# untitled.net
KiCad netlist of a schematic drawn in EAGLE
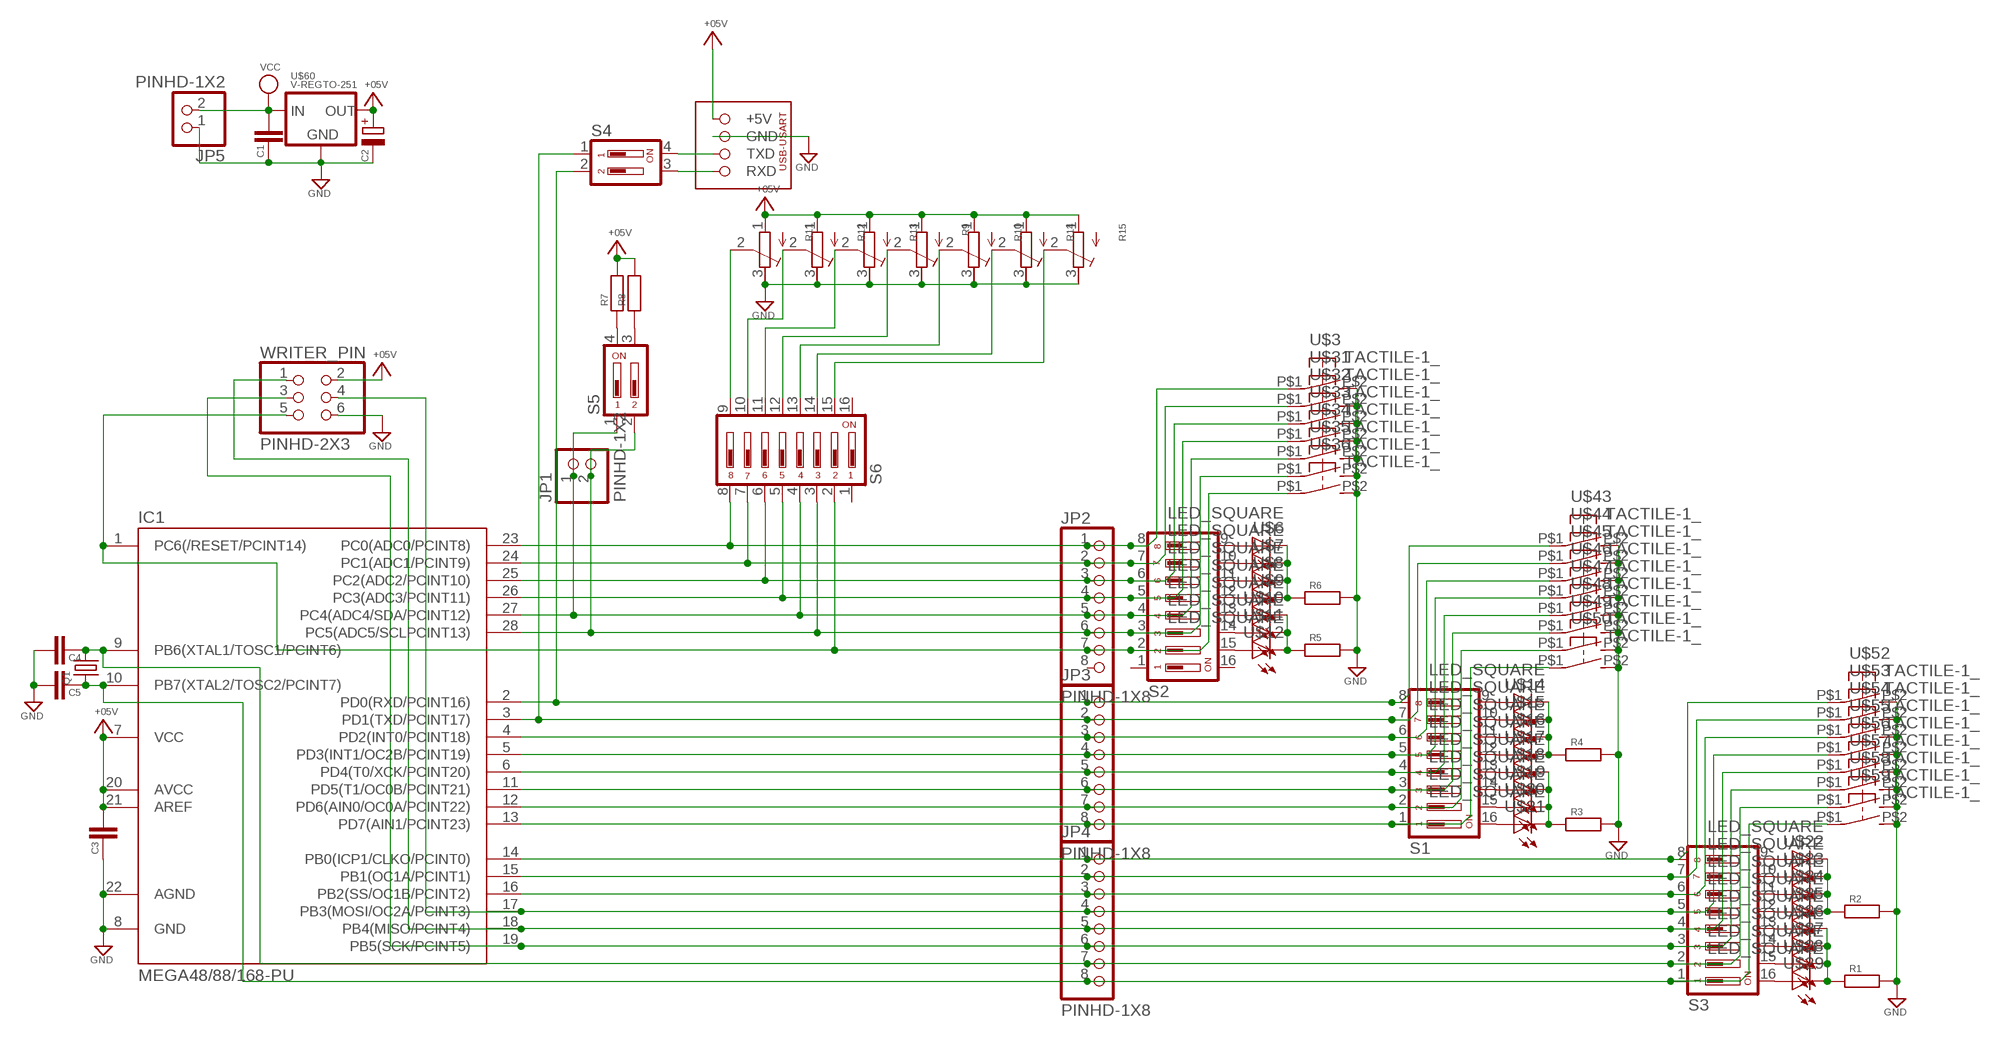
[diagram p0: schematic, sheet 1]

(export (version "E")
  (design (tool "Eeschema 10.0.6"))
  (components
    (comp (ref "C1")
      (value "C-025-025X050")
      (footprint "eagle-import:C025-025X050")
      (libsource (lib "eagle-import") (part "C-025-025X050"))
    )
    (comp (ref "C2")
      (value "CPOL-E2.5-6")
      (footprint "eagle-import:E2,5-6")
      (libsource (lib "eagle-import") (part "CPOL-E2.5-6"))
    )
    (comp (ref "C3")
      (value "C-025-025X050")
      (footprint "eagle-import:C025-025X050")
      (libsource (lib "eagle-import") (part "C-025-025X050"))
    )
    (comp (ref "C4")
      (value "C-025-025X050")
      (footprint "eagle-import:C025-025X050")
      (libsource (lib "eagle-import") (part "C-025-025X050"))
    )
    (comp (ref "C5")
      (value "C-025-025X050")
      (footprint "eagle-import:C025-025X050")
      (libsource (lib "eagle-import") (part "C-025-025X050"))
    )
    (comp (ref "IC1")
      (value "MEGA48/88/168-PU")
      (footprint "eagle-import:DIL28-3")
      (libsource (lib "eagle-import") (part "MEGA48/88/168-PU"))
    )
    (comp (ref "JP1")
      (value "PINHD-1X2")
      (footprint "eagle-import:1X02")
      (libsource (lib "eagle-import") (part "PINHD-1X2"))
    )
    (comp (ref "JP2")
      (value "PINHD-1X8")
      (footprint "eagle-import:1X08")
      (libsource (lib "eagle-import") (part "PINHD-1X8"))
    )
    (comp (ref "JP3")
      (value "PINHD-1X8")
      (footprint "eagle-import:1X08")
      (libsource (lib "eagle-import") (part "PINHD-1X8"))
    )
    (comp (ref "JP4")
      (value "PINHD-1X8")
      (footprint "eagle-import:1X08")
      (libsource (lib "eagle-import") (part "PINHD-1X8"))
    )
    (comp (ref "JP5")
      (value "PINHD-1X2")
      (footprint "eagle-import:1X02")
      (libsource (lib "eagle-import") (part "PINHD-1X2"))
    )
    (comp (ref "Q1")
      (value "CRYSTALHC49S")
      (footprint "eagle-import:HC49_S")
      (libsource (lib "eagle-import") (part "CRYSTALHC49S"))
    )
    (comp (ref "R1")
      (value "R-EU_1/4W(8MM)")
      (footprint "eagle-import:1_4W(8MM)")
      (libsource (lib "eagle-import") (part "R-EU_1/4W(8MM)"))
    )
    (comp (ref "R2")
      (value "R-EU_1/4W(8MM)")
      (footprint "eagle-import:1_4W(8MM)")
      (libsource (lib "eagle-import") (part "R-EU_1/4W(8MM)"))
    )
    (comp (ref "R3")
      (value "R-EU_1/4W(8MM)")
      (footprint "eagle-import:1_4W(8MM)")
      (libsource (lib "eagle-import") (part "R-EU_1/4W(8MM)"))
    )
    (comp (ref "R4")
      (value "R-EU_1/4W(8MM)")
      (footprint "eagle-import:1_4W(8MM)")
      (libsource (lib "eagle-import") (part "R-EU_1/4W(8MM)"))
    )
    (comp (ref "R5")
      (value "R-EU_1/4W(8MM)")
      (footprint "eagle-import:1_4W(8MM)")
      (libsource (lib "eagle-import") (part "R-EU_1/4W(8MM)"))
    )
    (comp (ref "R6")
      (value "R-EU_1/4W(8MM)")
      (footprint "eagle-import:1_4W(8MM)")
      (libsource (lib "eagle-import") (part "R-EU_1/4W(8MM)"))
    )
    (comp (ref "R7")
      (value "R-EU_1/4W(8MM)")
      (footprint "eagle-import:1_4W(8MM)")
      (libsource (lib "eagle-import") (part "R-EU_1/4W(8MM)"))
    )
    (comp (ref "R8")
      (value "R-EU_1/4W(8MM)")
      (footprint "eagle-import:1_4W(8MM)")
      (libsource (lib "eagle-import") (part "R-EU_1/4W(8MM)"))
    )
    (comp (ref "R9")
      (value "R-TRIMM_3339P")
      (footprint "eagle-import:3339P")
      (libsource (lib "eagle-import") (part "R-TRIMM_3339P"))
    )
    (comp (ref "R10")
      (value "R-TRIMM_3339P")
      (footprint "eagle-import:3339P")
      (libsource (lib "eagle-import") (part "R-TRIMM_3339P"))
    )
    (comp (ref "R11")
      (value "R-TRIMM_3339P")
      (footprint "eagle-import:3339P")
      (libsource (lib "eagle-import") (part "R-TRIMM_3339P"))
    )
    (comp (ref "R12")
      (value "R-TRIMM_3339P")
      (footprint "eagle-import:3339P")
      (libsource (lib "eagle-import") (part "R-TRIMM_3339P"))
    )
    (comp (ref "R13")
      (value "R-TRIMM_3339P")
      (footprint "eagle-import:3339P")
      (libsource (lib "eagle-import") (part "R-TRIMM_3339P"))
    )
    (comp (ref "R14")
      (value "R-TRIMM_3339P")
      (footprint "eagle-import:3339P")
      (libsource (lib "eagle-import") (part "R-TRIMM_3339P"))
    )
    (comp (ref "R15")
      (value "R-TRIMM_3339P")
      (footprint "eagle-import:3339P")
      (libsource (lib "eagle-import") (part "R-TRIMM_3339P"))
    )
    (comp (ref "S1")
      (value "DIP08YL")
      (footprint "eagle-import:DIP08YL")
      (libsource (lib "eagle-import") (part "DIP08YL"))
    )
    (comp (ref "S2")
      (value "DIP08YL")
      (footprint "eagle-import:DIP08YL")
      (libsource (lib "eagle-import") (part "DIP08YL"))
    )
    (comp (ref "S3")
      (value "DIP08YL")
      (footprint "eagle-import:DIP08YL")
      (libsource (lib "eagle-import") (part "DIP08YL"))
    )
    (comp (ref "S4")
      (value "DIP02YL")
      (footprint "eagle-import:DIP02YL")
      (libsource (lib "eagle-import") (part "DIP02YL"))
    )
    (comp (ref "S5")
      (value "DIP02YL")
      (footprint "eagle-import:DIP02YL")
      (libsource (lib "eagle-import") (part "DIP02YL"))
    )
    (comp (ref "S6")
      (value "DIP08YL")
      (footprint "eagle-import:DIP08YL")
      (libsource (lib "eagle-import") (part "DIP08YL"))
    )
    (comp (ref "U$3")
      (value "TACTILE-1_")
      (footprint "eagle-import:TACTILE_")
      (libsource (lib "eagle-import") (part "TACTILE-1_"))
    )
    (comp (ref "U$6")
      (value "LED_SQUARE")
      (footprint "eagle-import:5020")
      (libsource (lib "eagle-import") (part "LED_SQUARE"))
    )
    (comp (ref "U$7")
      (value "LED_SQUARE")
      (footprint "eagle-import:5020")
      (libsource (lib "eagle-import") (part "LED_SQUARE"))
    )
    (comp (ref "U$8")
      (value "LED_SQUARE")
      (footprint "eagle-import:5020")
      (libsource (lib "eagle-import") (part "LED_SQUARE"))
    )
    (comp (ref "U$9")
      (value "LED_SQUARE")
      (footprint "eagle-import:5020")
      (libsource (lib "eagle-import") (part "LED_SQUARE"))
    )
    (comp (ref "U$10")
      (value "LED_SQUARE")
      (footprint "eagle-import:5020")
      (libsource (lib "eagle-import") (part "LED_SQUARE"))
    )
    (comp (ref "U$11")
      (value "LED_SQUARE")
      (footprint "eagle-import:5020")
      (libsource (lib "eagle-import") (part "LED_SQUARE"))
    )
    (comp (ref "U$12")
      (value "LED_SQUARE")
      (footprint "eagle-import:5020")
      (libsource (lib "eagle-import") (part "LED_SQUARE"))
    )
    (comp (ref "U$14")
      (value "LED_SQUARE")
      (footprint "eagle-import:5020")
      (libsource (lib "eagle-import") (part "LED_SQUARE"))
    )
    (comp (ref "U$15")
      (value "LED_SQUARE")
      (footprint "eagle-import:5020")
      (libsource (lib "eagle-import") (part "LED_SQUARE"))
    )
    (comp (ref "U$16")
      (value "LED_SQUARE")
      (footprint "eagle-import:5020")
      (libsource (lib "eagle-import") (part "LED_SQUARE"))
    )
    (comp (ref "U$17")
      (value "LED_SQUARE")
      (footprint "eagle-import:5020")
      (libsource (lib "eagle-import") (part "LED_SQUARE"))
    )
    (comp (ref "U$18")
      (value "LED_SQUARE")
      (footprint "eagle-import:5020")
      (libsource (lib "eagle-import") (part "LED_SQUARE"))
    )
    (comp (ref "U$19")
      (value "LED_SQUARE")
      (footprint "eagle-import:5020")
      (libsource (lib "eagle-import") (part "LED_SQUARE"))
    )
    (comp (ref "U$20")
      (value "LED_SQUARE")
      (footprint "eagle-import:5020")
      (libsource (lib "eagle-import") (part "LED_SQUARE"))
    )
    (comp (ref "U$21")
      (value "LED_SQUARE")
      (footprint "eagle-import:5020")
      (libsource (lib "eagle-import") (part "LED_SQUARE"))
    )
    (comp (ref "U$22")
      (value "LED_SQUARE")
      (footprint "eagle-import:5020")
      (libsource (lib "eagle-import") (part "LED_SQUARE"))
    )
    (comp (ref "U$23")
      (value "LED_SQUARE")
      (footprint "eagle-import:5020")
      (libsource (lib "eagle-import") (part "LED_SQUARE"))
    )
    (comp (ref "U$24")
      (value "LED_SQUARE")
      (footprint "eagle-import:5020")
      (libsource (lib "eagle-import") (part "LED_SQUARE"))
    )
    (comp (ref "U$25")
      (value "LED_SQUARE")
      (footprint "eagle-import:5020")
      (libsource (lib "eagle-import") (part "LED_SQUARE"))
    )
    (comp (ref "U$26")
      (value "LED_SQUARE")
      (footprint "eagle-import:5020")
      (libsource (lib "eagle-import") (part "LED_SQUARE"))
    )
    (comp (ref "U$27")
      (value "LED_SQUARE")
      (footprint "eagle-import:5020")
      (libsource (lib "eagle-import") (part "LED_SQUARE"))
    )
    (comp (ref "U$28")
      (value "LED_SQUARE")
      (footprint "eagle-import:5020")
      (libsource (lib "eagle-import") (part "LED_SQUARE"))
    )
    (comp (ref "U$29")
      (value "LED_SQUARE")
      (footprint "eagle-import:5020")
      (libsource (lib "eagle-import") (part "LED_SQUARE"))
    )
    (comp (ref "U$31")
      (value "TACTILE-1_")
      (footprint "eagle-import:TACTILE_")
      (libsource (lib "eagle-import") (part "TACTILE-1_"))
    )
    (comp (ref "U$32")
      (value "TACTILE-1_")
      (footprint "eagle-import:TACTILE_")
      (libsource (lib "eagle-import") (part "TACTILE-1_"))
    )
    (comp (ref "U$33")
      (value "TACTILE-1_")
      (footprint "eagle-import:TACTILE_")
      (libsource (lib "eagle-import") (part "TACTILE-1_"))
    )
    (comp (ref "U$34")
      (value "TACTILE-1_")
      (footprint "eagle-import:TACTILE_")
      (libsource (lib "eagle-import") (part "TACTILE-1_"))
    )
    (comp (ref "U$35")
      (value "TACTILE-1_")
      (footprint "eagle-import:TACTILE_")
      (libsource (lib "eagle-import") (part "TACTILE-1_"))
    )
    (comp (ref "U$36")
      (value "TACTILE-1_")
      (footprint "eagle-import:TACTILE_")
      (libsource (lib "eagle-import") (part "TACTILE-1_"))
    )
    (comp (ref "U$43")
      (value "TACTILE-1_")
      (footprint "eagle-import:TACTILE_")
      (libsource (lib "eagle-import") (part "TACTILE-1_"))
    )
    (comp (ref "U$44")
      (value "TACTILE-1_")
      (footprint "eagle-import:TACTILE_")
      (libsource (lib "eagle-import") (part "TACTILE-1_"))
    )
    (comp (ref "U$45")
      (value "TACTILE-1_")
      (footprint "eagle-import:TACTILE_")
      (libsource (lib "eagle-import") (part "TACTILE-1_"))
    )
    (comp (ref "U$46")
      (value "TACTILE-1_")
      (footprint "eagle-import:TACTILE_")
      (libsource (lib "eagle-import") (part "TACTILE-1_"))
    )
    (comp (ref "U$47")
      (value "TACTILE-1_")
      (footprint "eagle-import:TACTILE_")
      (libsource (lib "eagle-import") (part "TACTILE-1_"))
    )
    (comp (ref "U$48")
      (value "TACTILE-1_")
      (footprint "eagle-import:TACTILE_")
      (libsource (lib "eagle-import") (part "TACTILE-1_"))
    )
    (comp (ref "U$49")
      (value "TACTILE-1_")
      (footprint "eagle-import:TACTILE_")
      (libsource (lib "eagle-import") (part "TACTILE-1_"))
    )
    (comp (ref "U$50")
      (value "TACTILE-1_")
      (footprint "eagle-import:TACTILE_")
      (libsource (lib "eagle-import") (part "TACTILE-1_"))
    )
    (comp (ref "U$52")
      (value "TACTILE-1_")
      (footprint "eagle-import:TACTILE_")
      (libsource (lib "eagle-import") (part "TACTILE-1_"))
    )
    (comp (ref "U$53")
      (value "TACTILE-1_")
      (footprint "eagle-import:TACTILE_")
      (libsource (lib "eagle-import") (part "TACTILE-1_"))
    )
    (comp (ref "U$54")
      (value "TACTILE-1_")
      (footprint "eagle-import:TACTILE_")
      (libsource (lib "eagle-import") (part "TACTILE-1_"))
    )
    (comp (ref "U$55")
      (value "TACTILE-1_")
      (footprint "eagle-import:TACTILE_")
      (libsource (lib "eagle-import") (part "TACTILE-1_"))
    )
    (comp (ref "U$56")
      (value "TACTILE-1_")
      (footprint "eagle-import:TACTILE_")
      (libsource (lib "eagle-import") (part "TACTILE-1_"))
    )
    (comp (ref "U$57")
      (value "TACTILE-1_")
      (footprint "eagle-import:TACTILE_")
      (libsource (lib "eagle-import") (part "TACTILE-1_"))
    )
    (comp (ref "U$58")
      (value "TACTILE-1_")
      (footprint "eagle-import:TACTILE_")
      (libsource (lib "eagle-import") (part "TACTILE-1_"))
    )
    (comp (ref "U$59")
      (value "TACTILE-1_")
      (footprint "eagle-import:TACTILE_")
      (libsource (lib "eagle-import") (part "TACTILE-1_"))
    )
    (comp (ref "U$60")
      (value "V-REGTO-251")
      (footprint "eagle-import:TO-251")
      (libsource (lib "eagle-import") (part "V-REGTO-251"))
    )
    (comp (ref "U$64")
      (value "AE-FT234X")
      (footprint "eagle-import:AE-FT234X")
      (libsource (lib "eagle-import") (part "AE-FT234X"))
    )
    (comp (ref "WRITER_PIN")
      (value "PINHD-2X3")
      (footprint "eagle-import:2X03")
      (libsource (lib "eagle-import") (part "PINHD-2X3"))
    )
  )
  (nets
    (net (code "1") (name "+05V") (class "Default")
      (node (ref "C2") (pin "+") (pinfunction "+_+") (pintype "passive"))
      (node (ref "C3") (pin "1") (pinfunction "1_1") (pintype "passive"))
      (node (ref "IC1") (pin "20") (pinfunction "AVCC_20") (pintype "passive"))
      (node (ref "IC1") (pin "21") (pinfunction "AREF_21") (pintype "passive"))
      (node (ref "IC1") (pin "7") (pinfunction "VCC_7") (pintype "power_in"))
      (node (ref "R10") (pin "1") (pinfunction "E_1") (pintype "passive"))
      (node (ref "R11") (pin "1") (pinfunction "E_1") (pintype "passive"))
      (node (ref "R12") (pin "1") (pinfunction "E_1") (pintype "passive"))
      (node (ref "R13") (pin "1") (pinfunction "E_1") (pintype "passive"))
      (node (ref "R14") (pin "1") (pinfunction "E_1") (pintype "passive"))
      (node (ref "R15") (pin "1") (pinfunction "E_1") (pintype "passive"))
      (node (ref "R7") (pin "2") (pinfunction "2_2") (pintype "passive"))
      (node (ref "R8") (pin "2") (pinfunction "2_2") (pintype "passive"))
      (node (ref "R9") (pin "1") (pinfunction "E_1") (pintype "passive"))
      (node (ref "U$60") (pin "3") (pinfunction "OUT_3") (pintype "passive"))
      (node (ref "U$64") (pin "P$1") (pinfunction "+5V_P$1") (pintype "bidirectional"))
      (node (ref "WRITER_PIN") (pin "2") (pinfunction "2_2") (pintype "passive"))
    )
    (net (code "2") (name "GND") (class "Default")
      (node (ref "C1") (pin "2") (pinfunction "2_2") (pintype "passive"))
      (node (ref "C2") (pin "-") (pinfunction "-_-") (pintype "passive"))
      (node (ref "C3") (pin "2") (pinfunction "2_2") (pintype "passive"))
      (node (ref "C4") (pin "1") (pinfunction "1_1") (pintype "passive"))
      (node (ref "C5") (pin "1") (pinfunction "1_1") (pintype "passive"))
      (node (ref "IC1") (pin "22") (pinfunction "AGND_22") (pintype "power_in"))
      (node (ref "IC1") (pin "8") (pinfunction "GND_8") (pintype "power_in"))
      (node (ref "JP5") (pin "1") (pinfunction "1_1") (pintype "passive"))
      (node (ref "R1") (pin "2") (pinfunction "2_2") (pintype "passive"))
      (node (ref "R10") (pin "3") (pinfunction "A_3") (pintype "passive"))
      (node (ref "R11") (pin "3") (pinfunction "A_3") (pintype "passive"))
      (node (ref "R12") (pin "3") (pinfunction "A_3") (pintype "passive"))
      (node (ref "R13") (pin "3") (pinfunction "A_3") (pintype "passive"))
      (node (ref "R14") (pin "3") (pinfunction "A_3") (pintype "passive"))
      (node (ref "R15") (pin "3") (pinfunction "A_3") (pintype "passive"))
      (node (ref "R2") (pin "2") (pinfunction "2_2") (pintype "passive"))
      (node (ref "R3") (pin "2") (pinfunction "2_2") (pintype "passive"))
      (node (ref "R4") (pin "2") (pinfunction "2_2") (pintype "passive"))
      (node (ref "R5") (pin "2") (pinfunction "2_2") (pintype "passive"))
      (node (ref "R6") (pin "2") (pinfunction "2_2") (pintype "passive"))
      (node (ref "R9") (pin "3") (pinfunction "A_3") (pintype "passive"))
      (node (ref "U$3") (pin "P$2") (pinfunction "S_P$2") (pintype "passive"))
      (node (ref "U$31") (pin "P$2") (pinfunction "S_P$2") (pintype "passive"))
      (node (ref "U$32") (pin "P$2") (pinfunction "S_P$2") (pintype "passive"))
      (node (ref "U$33") (pin "P$2") (pinfunction "S_P$2") (pintype "passive"))
      (node (ref "U$34") (pin "P$2") (pinfunction "S_P$2") (pintype "passive"))
      (node (ref "U$35") (pin "P$2") (pinfunction "S_P$2") (pintype "passive"))
      (node (ref "U$36") (pin "P$2") (pinfunction "S_P$2") (pintype "passive"))
      (node (ref "U$43") (pin "P$2") (pinfunction "S_P$2") (pintype "passive"))
      (node (ref "U$44") (pin "P$2") (pinfunction "S_P$2") (pintype "passive"))
      (node (ref "U$45") (pin "P$2") (pinfunction "S_P$2") (pintype "passive"))
      (node (ref "U$46") (pin "P$2") (pinfunction "S_P$2") (pintype "passive"))
      (node (ref "U$47") (pin "P$2") (pinfunction "S_P$2") (pintype "passive"))
      (node (ref "U$48") (pin "P$2") (pinfunction "S_P$2") (pintype "passive"))
      (node (ref "U$49") (pin "P$2") (pinfunction "S_P$2") (pintype "passive"))
      (node (ref "U$50") (pin "P$2") (pinfunction "S_P$2") (pintype "passive"))
      (node (ref "U$52") (pin "P$2") (pinfunction "S_P$2") (pintype "passive"))
      (node (ref "U$53") (pin "P$2") (pinfunction "S_P$2") (pintype "passive"))
      (node (ref "U$54") (pin "P$2") (pinfunction "S_P$2") (pintype "passive"))
      (node (ref "U$55") (pin "P$2") (pinfunction "S_P$2") (pintype "passive"))
      (node (ref "U$56") (pin "P$2") (pinfunction "S_P$2") (pintype "passive"))
      (node (ref "U$57") (pin "P$2") (pinfunction "S_P$2") (pintype "passive"))
      (node (ref "U$58") (pin "P$2") (pinfunction "S_P$2") (pintype "passive"))
      (node (ref "U$59") (pin "P$2") (pinfunction "S_P$2") (pintype "passive"))
      (node (ref "U$60") (pin "2") (pinfunction "GND_2") (pintype "input"))
      (node (ref "U$64") (pin "P$2") (pinfunction "GND_P$2") (pintype "bidirectional"))
      (node (ref "WRITER_PIN") (pin "6") (pinfunction "6_6") (pintype "passive"))
    )
    (net (code "3") (name "Net-(IC1-PB0(ICP1{slash}CLKO{slash}PCINT0))") (class "Default")
      (node (ref "IC1") (pin "14") (pinfunction "PB0(ICP1/CLKO/PCINT0)_14") (pintype "bidirectional"))
      (node (ref "JP4") (pin "1") (pinfunction "1_1") (pintype "passive"))
      (node (ref "S3") (pin "8") (pinfunction "8_8") (pintype "passive"))
      (node (ref "U$52") (pin "P$1") (pinfunction "P_P$1") (pintype "passive"))
    )
    (net (code "4") (name "Net-(IC1-PB1(OC1A{slash}PCINT1))") (class "Default")
      (node (ref "IC1") (pin "15") (pinfunction "PB1(OC1A/PCINT1)_15") (pintype "bidirectional"))
      (node (ref "JP4") (pin "2") (pinfunction "2_2") (pintype "passive"))
      (node (ref "S3") (pin "7") (pinfunction "7_7") (pintype "passive"))
      (node (ref "U$53") (pin "P$1") (pinfunction "P_P$1") (pintype "passive"))
    )
    (net (code "5") (name "Net-(IC1-PB2(SS{slash}OC1B{slash}PCINT2))") (class "Default")
      (node (ref "IC1") (pin "16") (pinfunction "PB2(SS/OC1B/PCINT2)_16") (pintype "bidirectional"))
      (node (ref "JP4") (pin "3") (pinfunction "3_3") (pintype "passive"))
      (node (ref "S3") (pin "6") (pinfunction "6_6") (pintype "passive"))
      (node (ref "U$54") (pin "P$1") (pinfunction "P_P$1") (pintype "passive"))
    )
    (net (code "6") (name "Net-(IC1-PB3(MOSI{slash}OC2A{slash}PCINT3))") (class "Default")
      (node (ref "IC1") (pin "17") (pinfunction "PB3(MOSI/OC2A/PCINT3)_17") (pintype "bidirectional"))
      (node (ref "JP4") (pin "4") (pinfunction "4_4") (pintype "passive"))
      (node (ref "S3") (pin "5") (pinfunction "5_5") (pintype "passive"))
      (node (ref "U$55") (pin "P$1") (pinfunction "P_P$1") (pintype "passive"))
      (node (ref "WRITER_PIN") (pin "4") (pinfunction "4_4") (pintype "passive"))
    )
    (net (code "7") (name "Net-(IC1-PB4(MISO{slash}PCINT4))") (class "Default")
      (node (ref "IC1") (pin "18") (pinfunction "PB4(MISO/PCINT4)_18") (pintype "bidirectional"))
      (node (ref "JP4") (pin "5") (pinfunction "5_5") (pintype "passive"))
      (node (ref "S3") (pin "4") (pinfunction "4_4") (pintype "passive"))
      (node (ref "U$56") (pin "P$1") (pinfunction "P_P$1") (pintype "passive"))
      (node (ref "WRITER_PIN") (pin "1") (pinfunction "1_1") (pintype "passive"))
    )
    (net (code "8") (name "Net-(IC1-PB5(SCK{slash}PCINT5))") (class "Default")
      (node (ref "IC1") (pin "19") (pinfunction "PB5(SCK/PCINT5)_19") (pintype "bidirectional"))
      (node (ref "JP4") (pin "6") (pinfunction "6_6") (pintype "passive"))
      (node (ref "S3") (pin "3") (pinfunction "3_3") (pintype "passive"))
      (node (ref "U$57") (pin "P$1") (pinfunction "P_P$1") (pintype "passive"))
      (node (ref "WRITER_PIN") (pin "3") (pinfunction "3_3") (pintype "passive"))
    )
    (net (code "9") (name "Net-(IC1-PB6(XTAL1{slash}TOSC1{slash}PCINT6))") (class "Default")
      (node (ref "C4") (pin "2") (pinfunction "2_2") (pintype "passive"))
      (node (ref "IC1") (pin "9") (pinfunction "PB6(XTAL1/TOSC1/PCINT6)_9") (pintype "bidirectional"))
      (node (ref "JP4") (pin "7") (pinfunction "7_7") (pintype "passive"))
      (node (ref "Q1") (pin "2") (pinfunction "2_2") (pintype "passive"))
      (node (ref "S3") (pin "2") (pinfunction "2_2") (pintype "passive"))
      (node (ref "U$58") (pin "P$1") (pinfunction "P_P$1") (pintype "passive"))
    )
    (net (code "10") (name "Net-(IC1-PB7(XTAL2{slash}TOSC2{slash}PCINT7))") (class "Default")
      (node (ref "C5") (pin "2") (pinfunction "2_2") (pintype "passive"))
      (node (ref "IC1") (pin "10") (pinfunction "PB7(XTAL2/TOSC2/PCINT7)_10") (pintype "bidirectional"))
      (node (ref "JP4") (pin "8") (pinfunction "8_8") (pintype "passive"))
      (node (ref "Q1") (pin "1") (pinfunction "1_1") (pintype "passive"))
      (node (ref "S3") (pin "1") (pinfunction "1_1") (pintype "passive"))
      (node (ref "U$59") (pin "P$1") (pinfunction "P_P$1") (pintype "passive"))
    )
    (net (code "11") (name "Net-(IC1-PC0(ADC0{slash}PCINT8))") (class "Default")
      (node (ref "IC1") (pin "23") (pinfunction "PC0(ADC0/PCINT8)_23") (pintype "bidirectional"))
      (node (ref "JP2") (pin "1") (pinfunction "1_1") (pintype "passive"))
      (node (ref "S2") (pin "8") (pinfunction "8_8") (pintype "passive"))
      (node (ref "S6") (pin "8") (pinfunction "8_8") (pintype "passive"))
      (node (ref "U$3") (pin "P$1") (pinfunction "P_P$1") (pintype "passive"))
    )
    (net (code "12") (name "Net-(IC1-PC1(ADC1{slash}PCINT9))") (class "Default")
      (node (ref "IC1") (pin "24") (pinfunction "PC1(ADC1/PCINT9)_24") (pintype "bidirectional"))
      (node (ref "JP2") (pin "2") (pinfunction "2_2") (pintype "passive"))
      (node (ref "S2") (pin "7") (pinfunction "7_7") (pintype "passive"))
      (node (ref "S6") (pin "7") (pinfunction "7_7") (pintype "passive"))
      (node (ref "U$31") (pin "P$1") (pinfunction "P_P$1") (pintype "passive"))
    )
    (net (code "13") (name "Net-(IC1-PC2(ADC2{slash}PCINT10))") (class "Default")
      (node (ref "IC1") (pin "25") (pinfunction "PC2(ADC2/PCINT10)_25") (pintype "bidirectional"))
      (node (ref "JP2") (pin "3") (pinfunction "3_3") (pintype "passive"))
      (node (ref "S2") (pin "6") (pinfunction "6_6") (pintype "passive"))
      (node (ref "S6") (pin "6") (pinfunction "6_6") (pintype "passive"))
      (node (ref "U$32") (pin "P$1") (pinfunction "P_P$1") (pintype "passive"))
    )
    (net (code "14") (name "Net-(IC1-PC3(ADC3{slash}PCINT11))") (class "Default")
      (node (ref "IC1") (pin "26") (pinfunction "PC3(ADC3/PCINT11)_26") (pintype "bidirectional"))
      (node (ref "JP2") (pin "4") (pinfunction "4_4") (pintype "passive"))
      (node (ref "S2") (pin "5") (pinfunction "5_5") (pintype "passive"))
      (node (ref "S6") (pin "5") (pinfunction "5_5") (pintype "passive"))
      (node (ref "U$33") (pin "P$1") (pinfunction "P_P$1") (pintype "passive"))
    )
    (net (code "15") (name "Net-(IC1-PC4(ADC4{slash}SDA{slash}PCINT12))") (class "Default")
      (node (ref "IC1") (pin "27") (pinfunction "PC4(ADC4/SDA/PCINT12)_27") (pintype "bidirectional"))
      (node (ref "JP1") (pin "1") (pinfunction "1_1") (pintype "passive"))
      (node (ref "JP2") (pin "5") (pinfunction "5_5") (pintype "passive"))
      (node (ref "S2") (pin "4") (pinfunction "4_4") (pintype "passive"))
      (node (ref "S5") (pin "1") (pinfunction "1_1") (pintype "passive"))
      (node (ref "S6") (pin "4") (pinfunction "4_4") (pintype "passive"))
      (node (ref "U$34") (pin "P$1") (pinfunction "P_P$1") (pintype "passive"))
    )
    (net (code "16") (name "Net-(IC1-PC5(ADC5{slash}SCLPCINT13))") (class "Default")
      (node (ref "IC1") (pin "28") (pinfunction "PC5(ADC5/SCLPCINT13)_28") (pintype "bidirectional"))
      (node (ref "JP1") (pin "2") (pinfunction "2_2") (pintype "passive"))
      (node (ref "JP2") (pin "6") (pinfunction "6_6") (pintype "passive"))
      (node (ref "S2") (pin "3") (pinfunction "3_3") (pintype "passive"))
      (node (ref "S5") (pin "2") (pinfunction "2_2") (pintype "passive"))
      (node (ref "S6") (pin "3") (pinfunction "3_3") (pintype "passive"))
      (node (ref "U$35") (pin "P$1") (pinfunction "P_P$1") (pintype "passive"))
    )
    (net (code "17") (name "Net-(IC1-PC6({slash}RESET{slash}PCINT14))") (class "Default")
      (node (ref "IC1") (pin "1") (pinfunction "PC6(/RESET/PCINT14)_1") (pintype "bidirectional"))
      (node (ref "JP2") (pin "7") (pinfunction "7_7") (pintype "passive"))
      (node (ref "S2") (pin "2") (pinfunction "2_2") (pintype "passive"))
      (node (ref "S6") (pin "2") (pinfunction "2_2") (pintype "passive"))
      (node (ref "U$36") (pin "P$1") (pinfunction "P_P$1") (pintype "passive"))
      (node (ref "WRITER_PIN") (pin "5") (pinfunction "5_5") (pintype "passive"))
    )
    (net (code "18") (name "Net-(IC1-PD0(RXD{slash}PCINT16))") (class "Default")
      (node (ref "IC1") (pin "2") (pinfunction "PD0(RXD/PCINT16)_2") (pintype "bidirectional"))
      (node (ref "JP3") (pin "1") (pinfunction "1_1") (pintype "passive"))
      (node (ref "S1") (pin "8") (pinfunction "8_8") (pintype "passive"))
      (node (ref "S4") (pin "2") (pinfunction "2_2") (pintype "passive"))
      (node (ref "U$43") (pin "P$1") (pinfunction "P_P$1") (pintype "passive"))
    )
    (net (code "19") (name "Net-(IC1-PD1(TXD{slash}PCINT17))") (class "Default")
      (node (ref "IC1") (pin "3") (pinfunction "PD1(TXD/PCINT17)_3") (pintype "bidirectional"))
      (node (ref "JP3") (pin "2") (pinfunction "2_2") (pintype "passive"))
      (node (ref "S1") (pin "7") (pinfunction "7_7") (pintype "passive"))
      (node (ref "S4") (pin "1") (pinfunction "1_1") (pintype "passive"))
      (node (ref "U$44") (pin "P$1") (pinfunction "P_P$1") (pintype "passive"))
    )
    (net (code "20") (name "Net-(IC1-PD2(INT0{slash}PCINT18))") (class "Default")
      (node (ref "IC1") (pin "4") (pinfunction "PD2(INT0/PCINT18)_4") (pintype "bidirectional"))
      (node (ref "JP3") (pin "3") (pinfunction "3_3") (pintype "passive"))
      (node (ref "S1") (pin "6") (pinfunction "6_6") (pintype "passive"))
      (node (ref "U$45") (pin "P$1") (pinfunction "P_P$1") (pintype "passive"))
    )
    (net (code "21") (name "Net-(IC1-PD3(INT1{slash}OC2B{slash}PCINT19))") (class "Default")
      (node (ref "IC1") (pin "5") (pinfunction "PD3(INT1/OC2B/PCINT19)_5") (pintype "bidirectional"))
      (node (ref "JP3") (pin "4") (pinfunction "4_4") (pintype "passive"))
      (node (ref "S1") (pin "5") (pinfunction "5_5") (pintype "passive"))
      (node (ref "U$46") (pin "P$1") (pinfunction "P_P$1") (pintype "passive"))
    )
    (net (code "22") (name "Net-(IC1-PD4(T0{slash}XCK{slash}PCINT20))") (class "Default")
      (node (ref "IC1") (pin "6") (pinfunction "PD4(T0/XCK/PCINT20)_6") (pintype "bidirectional"))
      (node (ref "JP3") (pin "5") (pinfunction "5_5") (pintype "passive"))
      (node (ref "S1") (pin "4") (pinfunction "4_4") (pintype "passive"))
      (node (ref "U$47") (pin "P$1") (pinfunction "P_P$1") (pintype "passive"))
    )
    (net (code "23") (name "Net-(IC1-PD5(T1{slash}OC0B{slash}PCINT21))") (class "Default")
      (node (ref "IC1") (pin "11") (pinfunction "PD5(T1/OC0B/PCINT21)_11") (pintype "bidirectional"))
      (node (ref "JP3") (pin "6") (pinfunction "6_6") (pintype "passive"))
      (node (ref "S1") (pin "3") (pinfunction "3_3") (pintype "passive"))
      (node (ref "U$48") (pin "P$1") (pinfunction "P_P$1") (pintype "passive"))
    )
    (net (code "24") (name "Net-(IC1-PD6(AIN0{slash}OC0A{slash}PCINT22))") (class "Default")
      (node (ref "IC1") (pin "12") (pinfunction "PD6(AIN0/OC0A/PCINT22)_12") (pintype "bidirectional"))
      (node (ref "JP3") (pin "7") (pinfunction "7_7") (pintype "passive"))
      (node (ref "S1") (pin "2") (pinfunction "2_2") (pintype "passive"))
      (node (ref "U$49") (pin "P$1") (pinfunction "P_P$1") (pintype "passive"))
    )
    (net (code "25") (name "Net-(IC1-PD7(AIN1{slash}PCINT23))") (class "Default")
      (node (ref "IC1") (pin "13") (pinfunction "PD7(AIN1/PCINT23)_13") (pintype "bidirectional"))
      (node (ref "JP3") (pin "8") (pinfunction "8_8") (pintype "passive"))
      (node (ref "S1") (pin "1") (pinfunction "1_1") (pintype "passive"))
      (node (ref "U$50") (pin "P$1") (pinfunction "P_P$1") (pintype "passive"))
    )
    (net (code "26") (name "Net-(R7-Pad1)") (class "Default")
      (node (ref "R7") (pin "1") (pinfunction "1_1") (pintype "passive"))
      (node (ref "S5") (pin "4") (pinfunction "4_4") (pintype "passive"))
    )
    (net (code "27") (name "Net-(R8-Pad1)") (class "Default")
      (node (ref "R8") (pin "1") (pinfunction "1_1") (pintype "passive"))
      (node (ref "S5") (pin "3") (pinfunction "3_3") (pintype "passive"))
    )
    (net (code "28") (name "Net-(R9-S)") (class "Default")
      (node (ref "R9") (pin "2") (pinfunction "S_2") (pintype "passive"))
      (node (ref "S6") (pin "12") (pinfunction "12_12") (pintype "passive"))
    )
    (net (code "29") (name "Net-(R10-S)") (class "Default")
      (node (ref "R10") (pin "2") (pinfunction "S_2") (pintype "passive"))
      (node (ref "S6") (pin "13") (pinfunction "13_13") (pintype "passive"))
    )
    (net (code "30") (name "Net-(R11-S)") (class "Default")
      (node (ref "R11") (pin "2") (pinfunction "S_2") (pintype "passive"))
      (node (ref "S6") (pin "9") (pinfunction "9_9") (pintype "passive"))
    )
    (net (code "31") (name "Net-(R12-S)") (class "Default")
      (node (ref "R12") (pin "2") (pinfunction "S_2") (pintype "passive"))
      (node (ref "S6") (pin "10") (pinfunction "10_10") (pintype "passive"))
    )
    (net (code "32") (name "Net-(R13-S)") (class "Default")
      (node (ref "R13") (pin "2") (pinfunction "S_2") (pintype "passive"))
      (node (ref "S6") (pin "11") (pinfunction "11_11") (pintype "passive"))
    )
    (net (code "33") (name "Net-(R14-S)") (class "Default")
      (node (ref "R14") (pin "2") (pinfunction "S_2") (pintype "passive"))
      (node (ref "S6") (pin "14") (pinfunction "14_14") (pintype "passive"))
    )
    (net (code "34") (name "Net-(R15-S)") (class "Default")
      (node (ref "R15") (pin "2") (pinfunction "S_2") (pintype "passive"))
      (node (ref "S6") (pin "15") (pinfunction "15_15") (pintype "passive"))
    )
    (net (code "35") (name "Net-(U$6-A)") (class "Default")
      (node (ref "S2") (pin "9") (pinfunction "9_9") (pintype "passive"))
      (node (ref "U$6") (pin "P$1") (pinfunction "A_P$1") (pintype "passive"))
    )
    (net (code "36") (name "Net-(U$6-C)") (class "Default")
      (node (ref "R6") (pin "1") (pinfunction "1_1") (pintype "passive"))
      (node (ref "U$6") (pin "P$2") (pinfunction "C_P$2") (pintype "passive"))
      (node (ref "U$7") (pin "P$2") (pinfunction "C_P$2") (pintype "passive"))
      (node (ref "U$8") (pin "P$2") (pinfunction "C_P$2") (pintype "passive"))
      (node (ref "U$9") (pin "P$2") (pinfunction "C_P$2") (pintype "passive"))
    )
    (net (code "37") (name "Net-(U$7-A)") (class "Default")
      (node (ref "S2") (pin "10") (pinfunction "10_10") (pintype "passive"))
      (node (ref "U$7") (pin "P$1") (pinfunction "A_P$1") (pintype "passive"))
    )
    (net (code "38") (name "Net-(U$8-A)") (class "Default")
      (node (ref "S2") (pin "11") (pinfunction "11_11") (pintype "passive"))
      (node (ref "U$8") (pin "P$1") (pinfunction "A_P$1") (pintype "passive"))
    )
    (net (code "39") (name "Net-(U$9-A)") (class "Default")
      (node (ref "S2") (pin "12") (pinfunction "12_12") (pintype "passive"))
      (node (ref "U$9") (pin "P$1") (pinfunction "A_P$1") (pintype "passive"))
    )
    (net (code "40") (name "Net-(U$10-A)") (class "Default")
      (node (ref "S2") (pin "13") (pinfunction "13_13") (pintype "passive"))
      (node (ref "U$10") (pin "P$1") (pinfunction "A_P$1") (pintype "passive"))
    )
    (net (code "41") (name "Net-(U$10-C)") (class "Default")
      (node (ref "R5") (pin "1") (pinfunction "1_1") (pintype "passive"))
      (node (ref "U$10") (pin "P$2") (pinfunction "C_P$2") (pintype "passive"))
      (node (ref "U$11") (pin "P$2") (pinfunction "C_P$2") (pintype "passive"))
      (node (ref "U$12") (pin "P$2") (pinfunction "C_P$2") (pintype "passive"))
    )
    (net (code "42") (name "Net-(U$11-A)") (class "Default")
      (node (ref "S2") (pin "14") (pinfunction "14_14") (pintype "passive"))
      (node (ref "U$11") (pin "P$1") (pinfunction "A_P$1") (pintype "passive"))
    )
    (net (code "43") (name "Net-(U$12-A)") (class "Default")
      (node (ref "S2") (pin "15") (pinfunction "15_15") (pintype "passive"))
      (node (ref "U$12") (pin "P$1") (pinfunction "A_P$1") (pintype "passive"))
    )
    (net (code "44") (name "Net-(U$14-A)") (class "Default")
      (node (ref "S1") (pin "9") (pinfunction "9_9") (pintype "passive"))
      (node (ref "U$14") (pin "P$1") (pinfunction "A_P$1") (pintype "passive"))
    )
    (net (code "45") (name "Net-(U$14-C)") (class "Default")
      (node (ref "R4") (pin "1") (pinfunction "1_1") (pintype "passive"))
      (node (ref "U$14") (pin "P$2") (pinfunction "C_P$2") (pintype "passive"))
      (node (ref "U$15") (pin "P$2") (pinfunction "C_P$2") (pintype "passive"))
      (node (ref "U$16") (pin "P$2") (pinfunction "C_P$2") (pintype "passive"))
      (node (ref "U$17") (pin "P$2") (pinfunction "C_P$2") (pintype "passive"))
    )
    (net (code "46") (name "Net-(U$15-A)") (class "Default")
      (node (ref "S1") (pin "10") (pinfunction "10_10") (pintype "passive"))
      (node (ref "U$15") (pin "P$1") (pinfunction "A_P$1") (pintype "passive"))
    )
    (net (code "47") (name "Net-(U$16-A)") (class "Default")
      (node (ref "S1") (pin "11") (pinfunction "11_11") (pintype "passive"))
      (node (ref "U$16") (pin "P$1") (pinfunction "A_P$1") (pintype "passive"))
    )
    (net (code "48") (name "Net-(U$17-A)") (class "Default")
      (node (ref "S1") (pin "12") (pinfunction "12_12") (pintype "passive"))
      (node (ref "U$17") (pin "P$1") (pinfunction "A_P$1") (pintype "passive"))
    )
    (net (code "49") (name "Net-(U$18-A)") (class "Default")
      (node (ref "S1") (pin "13") (pinfunction "13_13") (pintype "passive"))
      (node (ref "U$18") (pin "P$1") (pinfunction "A_P$1") (pintype "passive"))
    )
    (net (code "50") (name "Net-(U$18-C)") (class "Default")
      (node (ref "R3") (pin "1") (pinfunction "1_1") (pintype "passive"))
      (node (ref "U$18") (pin "P$2") (pinfunction "C_P$2") (pintype "passive"))
      (node (ref "U$19") (pin "P$2") (pinfunction "C_P$2") (pintype "passive"))
      (node (ref "U$20") (pin "P$2") (pinfunction "C_P$2") (pintype "passive"))
      (node (ref "U$21") (pin "P$2") (pinfunction "C_P$2") (pintype "passive"))
    )
    (net (code "51") (name "Net-(U$19-A)") (class "Default")
      (node (ref "S1") (pin "14") (pinfunction "14_14") (pintype "passive"))
      (node (ref "U$19") (pin "P$1") (pinfunction "A_P$1") (pintype "passive"))
    )
    (net (code "52") (name "Net-(U$20-A)") (class "Default")
      (node (ref "S1") (pin "15") (pinfunction "15_15") (pintype "passive"))
      (node (ref "U$20") (pin "P$1") (pinfunction "A_P$1") (pintype "passive"))
    )
    (net (code "53") (name "Net-(U$21-A)") (class "Default")
      (node (ref "S1") (pin "16") (pinfunction "16_16") (pintype "passive"))
      (node (ref "U$21") (pin "P$1") (pinfunction "A_P$1") (pintype "passive"))
    )
    (net (code "54") (name "Net-(U$22-A)") (class "Default")
      (node (ref "S3") (pin "9") (pinfunction "9_9") (pintype "passive"))
      (node (ref "U$22") (pin "P$1") (pinfunction "A_P$1") (pintype "passive"))
    )
    (net (code "55") (name "Net-(U$22-C)") (class "Default")
      (node (ref "R2") (pin "1") (pinfunction "1_1") (pintype "passive"))
      (node (ref "U$22") (pin "P$2") (pinfunction "C_P$2") (pintype "passive"))
      (node (ref "U$23") (pin "P$2") (pinfunction "C_P$2") (pintype "passive"))
      (node (ref "U$24") (pin "P$2") (pinfunction "C_P$2") (pintype "passive"))
      (node (ref "U$25") (pin "P$2") (pinfunction "C_P$2") (pintype "passive"))
    )
    (net (code "56") (name "Net-(U$23-A)") (class "Default")
      (node (ref "S3") (pin "10") (pinfunction "10_10") (pintype "passive"))
      (node (ref "U$23") (pin "P$1") (pinfunction "A_P$1") (pintype "passive"))
    )
    (net (code "57") (name "Net-(U$24-A)") (class "Default")
      (node (ref "S3") (pin "11") (pinfunction "11_11") (pintype "passive"))
      (node (ref "U$24") (pin "P$1") (pinfunction "A_P$1") (pintype "passive"))
    )
    (net (code "58") (name "Net-(U$25-A)") (class "Default")
      (node (ref "S3") (pin "12") (pinfunction "12_12") (pintype "passive"))
      (node (ref "U$25") (pin "P$1") (pinfunction "A_P$1") (pintype "passive"))
    )
    (net (code "59") (name "Net-(U$26-A)") (class "Default")
      (node (ref "S3") (pin "13") (pinfunction "13_13") (pintype "passive"))
      (node (ref "U$26") (pin "P$1") (pinfunction "A_P$1") (pintype "passive"))
    )
    (net (code "60") (name "Net-(U$26-C)") (class "Default")
      (node (ref "R1") (pin "1") (pinfunction "1_1") (pintype "passive"))
      (node (ref "U$26") (pin "P$2") (pinfunction "C_P$2") (pintype "passive"))
      (node (ref "U$27") (pin "P$2") (pinfunction "C_P$2") (pintype "passive"))
      (node (ref "U$28") (pin "P$2") (pinfunction "C_P$2") (pintype "passive"))
      (node (ref "U$29") (pin "P$2") (pinfunction "C_P$2") (pintype "passive"))
    )
    (net (code "61") (name "Net-(U$27-A)") (class "Default")
      (node (ref "S3") (pin "14") (pinfunction "14_14") (pintype "passive"))
      (node (ref "U$27") (pin "P$1") (pinfunction "A_P$1") (pintype "passive"))
    )
    (net (code "62") (name "Net-(U$28-A)") (class "Default")
      (node (ref "S3") (pin "15") (pinfunction "15_15") (pintype "passive"))
      (node (ref "U$28") (pin "P$1") (pinfunction "A_P$1") (pintype "passive"))
    )
    (net (code "63") (name "Net-(U$29-A)") (class "Default")
      (node (ref "S3") (pin "16") (pinfunction "16_16") (pintype "passive"))
      (node (ref "U$29") (pin "P$1") (pinfunction "A_P$1") (pintype "passive"))
    )
    (net (code "64") (name "Net-(U$64-RXD)") (class "Default")
      (node (ref "S4") (pin "3") (pinfunction "3_3") (pintype "passive"))
      (node (ref "U$64") (pin "P$4") (pinfunction "RXD_P$4") (pintype "bidirectional"))
    )
    (net (code "65") (name "Net-(U$64-TXD)") (class "Default")
      (node (ref "S4") (pin "4") (pinfunction "4_4") (pintype "passive"))
      (node (ref "U$64") (pin "P$3") (pinfunction "TXD_P$3") (pintype "bidirectional"))
    )
    (net (code "66") (name "VCC") (class "Default")
      (node (ref "C1") (pin "1") (pinfunction "1_1") (pintype "passive"))
      (node (ref "JP5") (pin "2") (pinfunction "2_2") (pintype "passive"))
      (node (ref "U$60") (pin "1") (pinfunction "IN_1") (pintype "input"))
    )
    (net (code "67") (name "unconnected-(JP2-Pad8)") (class "Default")
      (node (ref "JP2") (pin "8") (pinfunction "8_8") (pintype "passive"))
    )
    (net (code "68") (name "unconnected-(S2-Pad1)") (class "Default")
      (node (ref "S2") (pin "1") (pinfunction "1_1") (pintype "passive"))
    )
    (net (code "69") (name "unconnected-(S2-Pad16)") (class "Default")
      (node (ref "S2") (pin "16") (pinfunction "16_16") (pintype "passive"))
    )
    (net (code "70") (name "unconnected-(S6-Pad1)") (class "Default")
      (node (ref "S6") (pin "1") (pinfunction "1_1") (pintype "passive"))
    )
    (net (code "71") (name "unconnected-(S6-Pad16)") (class "Default")
      (node (ref "S6") (pin "16") (pinfunction "16_16") (pintype "passive"))
    )
  )
)
